# Relay_Board.net
KiCad netlist of a schematic drawn in Altium Designer
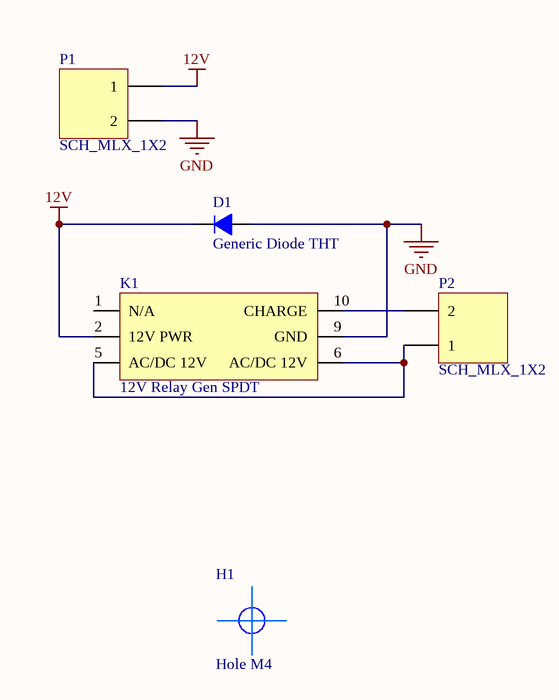
[diagram p0: Relay_Board.SchDoc]

(export (version "E")
  (design (tool "Eeschema 10.0.6"))
  (components
    (comp (ref "D1")
      (value "Generic Diode THT")
      (footprint "Generic Diode THT")
      (libsource (lib "Generic Diode THT") (part "Generic Diode THT"))
    )
    (comp (ref "H1") (value "Hole M4") (footprint "#10Hole") (libsource (lib "#10Hole") (part "#10Hole")))
    (comp (ref "K1")
      (value "12V Relay Gen SPDT")
      (footprint "12V Relay Gen SPDT")
      (libsource (lib "12V Relay Gen SPDT") (part "12V Relay Gen SPDT"))
    )
    (comp (ref "P1")
      (value "SCH_MLX_1X2")
      (footprint "PCB_MLX_MICROFIT_1X2")
      (libsource (lib "Molex Microfit 3.0 1x2") (part "SCH_MLX_1X2"))
    )
    (comp (ref "P2")
      (value "SCH_MLX_1X2")
      (footprint "PCB_MLX_MICROFIT_1X2")
      (libsource (lib "") (part "SCH_MLX_1X2_1"))
    )
  )
  (nets
    (net (code "1") (name "12V") (class "Default")
      (node (ref "D1") (pin "2") (pinfunction "2_2") (pintype "passive"))
      (node (ref "K1") (pin "2") (pinfunction "12V_PWR_2") (pintype "passive"))
      (node (ref "P1") (pin "1") (pinfunction "1_1") (pintype "passive"))
    )
    (net (code "2") (name "GND") (class "Default")
      (node (ref "D1") (pin "1") (pinfunction "1_1") (pintype "passive"))
      (node (ref "K1") (pin "9") (pinfunction "GND_9") (pintype "passive"))
      (node (ref "P1") (pin "2") (pinfunction "2_2") (pintype "passive"))
    )
    (net (code "3") (name "Net-(K1-AC{slash}DC_12V-Pad5)") (class "Default")
      (node (ref "K1") (pin "5") (pinfunction "AC/DC_12V_5") (pintype "passive"))
      (node (ref "K1") (pin "6") (pinfunction "AC/DC_12V_6") (pintype "passive"))
      (node (ref "P2") (pin "1") (pinfunction "1_1") (pintype "passive"))
    )
    (net (code "4") (name "Net-(K1-CHARGE)") (class "Default")
      (node (ref "K1") (pin "10") (pinfunction "CHARGE_10") (pintype "passive"))
      (node (ref "P2") (pin "2") (pinfunction "2_2") (pintype "passive"))
    )
    (net (code "5") (name "unconnected-(K1-N{slash}A-Pad1)") (class "Default")
      (node (ref "K1") (pin "1") (pinfunction "N/A_1") (pintype "passive"))
    )
  )
)
